# LIDO-HW_300_DisplayInterface.net
KiCad netlist of a schematic drawn in Altium Designer
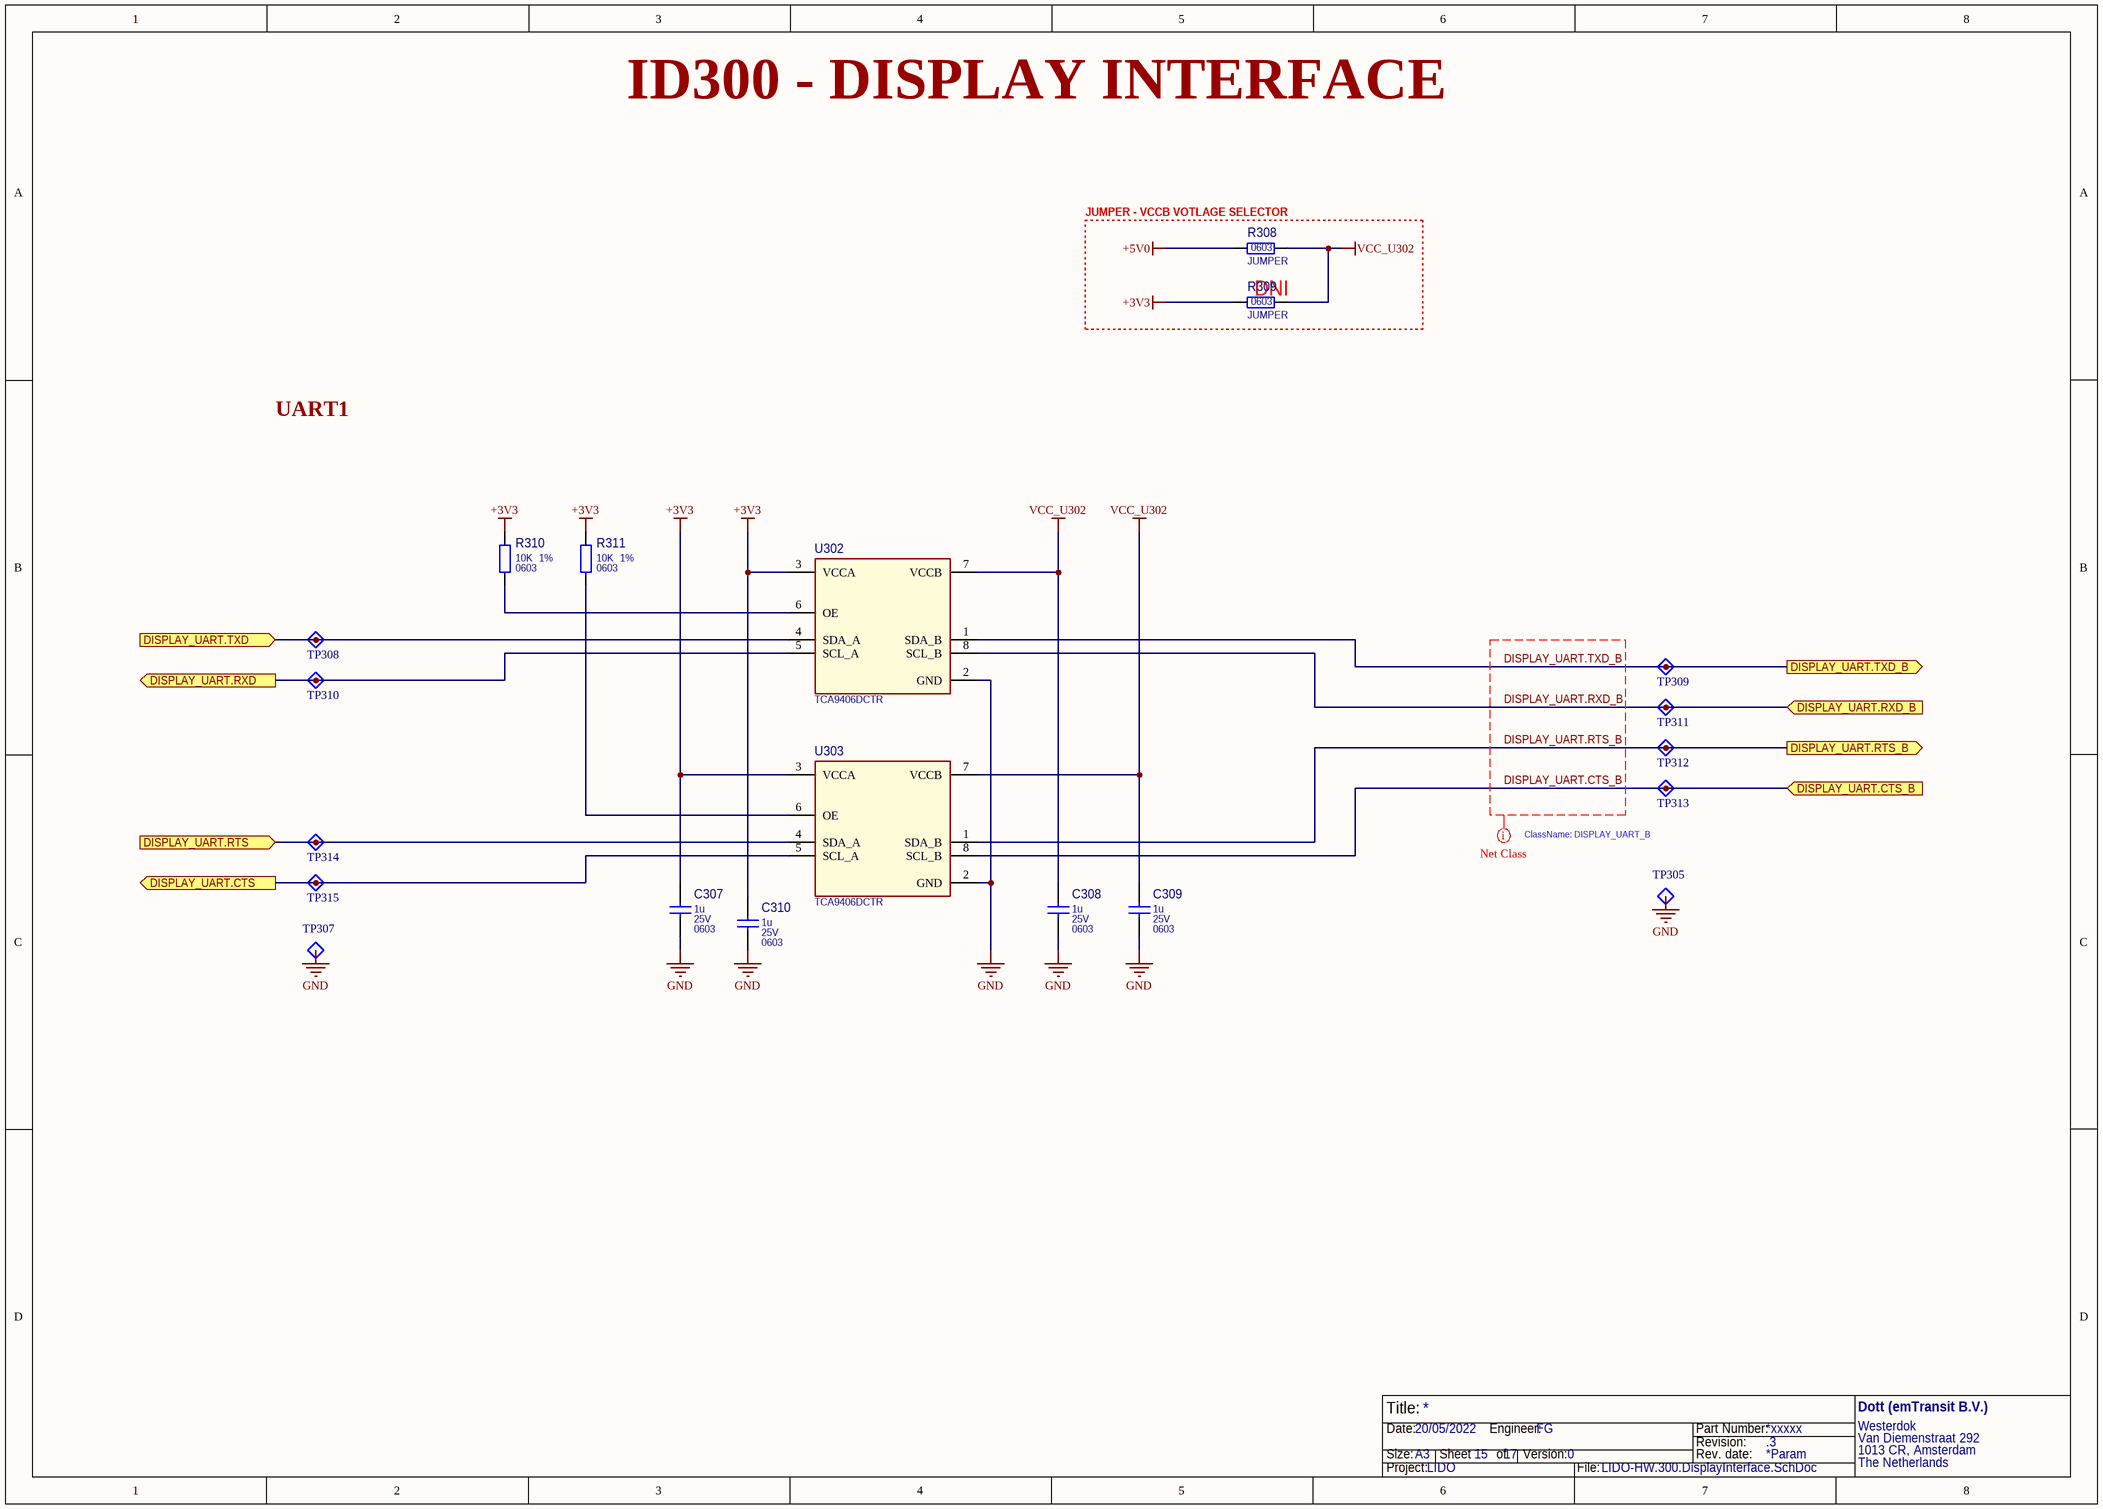
[diagram p0: LIDO-HW.300.DisplayInterface.SchDoc]

(export (version "E")
  (design (tool "Eeschema 10.0.6"))
  (components
    (comp (ref "C307")
      (value "1u")
      (footprint "CAP_0603_1608X90-N_MURATA_A")
      (description "CAP CER 1UF 25V X7R 0603")
      (fields
        (field (name "MANUFACTURER PART NUMBER") "CGA3E1X7R1E105M080AE")
        (field (name "MANUFACTURER") "TDK Corporation")
        (field (name "PART VALUE 2") "25V")
        (field (name "PART PACKAGE") "0603")
      )
      (libsource (lib "DB_Library") (part "Ceramic"))
    )
    (comp (ref "C308")
      (value "1u")
      (footprint "CAP_0603_1608X90-N_MURATA_A")
      (description "CAP CER 1UF 25V X7R 0603")
      (fields
        (field (name "MANUFACTURER PART NUMBER") "CGA3E1X7R1E105M080AE")
        (field (name "MANUFACTURER") "TDK Corporation")
        (field (name "PART VALUE 2") "25V")
        (field (name "PART PACKAGE") "0603")
      )
      (libsource (lib "DB_Library") (part "Ceramic"))
    )
    (comp (ref "C309")
      (value "1u")
      (footprint "CAP_0603_1608X90-N_MURATA_A")
      (description "CAP CER 1UF 25V X7R 0603")
      (fields
        (field (name "MANUFACTURER PART NUMBER") "CGA3E1X7R1E105M080AE")
        (field (name "MANUFACTURER") "TDK Corporation")
        (field (name "PART VALUE 2") "25V")
        (field (name "PART PACKAGE") "0603")
      )
      (libsource (lib "DB_Library") (part "Ceramic"))
    )
    (comp (ref "C310")
      (value "1u")
      (footprint "CAP_0603_1608X90-N_MURATA_A")
      (description "CAP CER 1UF 25V X7R 0603")
      (fields
        (field (name "MANUFACTURER PART NUMBER") "CGA3E1X7R1E105M080AE")
        (field (name "MANUFACTURER") "TDK Corporation")
        (field (name "PART VALUE 2") "25V")
        (field (name "PART PACKAGE") "0603")
      )
      (libsource (lib "DB_Library") (part "Ceramic"))
    )
    (comp (ref "R308")
      (value "JUMPER")
      (footprint "RES_0603_1608X60-N_YAGEO_A")
      (description "RES 0 OHM JUMPER 1/10W 0603")
      (fields
        (field (name "MANUFACTURER PART NUMBER") "RC0603JR-070RL")
        (field (name "MANUFACTURER") "YAGEO")
        (field (name "PART PACKAGE") "0603")
      )
      (libsource (lib "") (part "Resistor_1"))
    )
    (comp (ref "R309")
      (value "JUMPER")
      (footprint "RES_0603_1608X60-N_YAGEO_A")
      (description "RES 0 OHM JUMPER 1/10W 0603")
      (fields
        (field (name "MANUFACTURER PART NUMBER") "RC0603JR-070RL")
        (field (name "MANUFACTURER") "YAGEO")
        (field (name "PART PACKAGE") "0603")
      )
      (libsource (lib "") (part "Resistor_1"))
    )
    (comp (ref "R310")
      (value "10K")
      (footprint "RES_0603_1608X60-N_YAGEO_A")
      (description "RES 10K OHM 1% 1/10W 0603")
      (fields
        (field (name "MANUFACTURER PART NUMBER") "RC0603FR-0710KL")
        (field (name "MANUFACTURER") "YAGEO")
        (field (name "PART VALUE 2") "1%")
        (field (name "PART PACKAGE") "0603")
      )
      (libsource (lib "DB_Library") (part "Resistor"))
    )
    (comp (ref "R311")
      (value "10K")
      (footprint "RES_0603_1608X60-N_YAGEO_A")
      (description "RES 10K OHM 1% 1/10W 0603")
      (fields
        (field (name "MANUFACTURER PART NUMBER") "RC0603FR-0710KL")
        (field (name "MANUFACTURER") "YAGEO")
        (field (name "PART VALUE 2") "1%")
        (field (name "PART PACKAGE") "0603")
      )
      (libsource (lib "DB_Library") (part "Resistor"))
    )
    (comp (ref "TP305")
      (value "TestPoint_A")
      (footprint "TESTPOINT_1D_A")
      (description "Pad Diamater 1mm")
      (fields (field (name "PART") "Test Point 1D A") (field (name "OBSOLETE PART") "False"))
      (libsource (lib "DB_Library") (part "TestPoint_A"))
    )
    (comp (ref "TP307")
      (value "TestPoint_A")
      (footprint "TESTPOINT_1D_A")
      (description "Pad Diamater 1mm")
      (fields (field (name "PART") "Test Point 1D A") (field (name "OBSOLETE PART") "False"))
      (libsource (lib "DB_Library") (part "TestPoint_A"))
    )
    (comp (ref "TP308")
      (value "TestPoint_A")
      (footprint "TESTPOINT_1D_A")
      (description "Pad Diamater 1mm")
      (fields (field (name "PART") "Test Point 1D A") (field (name "OBSOLETE PART") "False"))
      (libsource (lib "DB_Library") (part "TestPoint_A"))
    )
    (comp (ref "TP309")
      (value "TestPoint_A")
      (footprint "TESTPOINT_1D_A")
      (description "Pad Diamater 1mm")
      (fields (field (name "PART") "Test Point 1D A") (field (name "OBSOLETE PART") "False"))
      (libsource (lib "DB_Library") (part "TestPoint_A"))
    )
    (comp (ref "TP310")
      (value "TestPoint_A")
      (footprint "TESTPOINT_1D_A")
      (description "Pad Diamater 1mm")
      (fields (field (name "PART") "Test Point 1D A") (field (name "OBSOLETE PART") "False"))
      (libsource (lib "DB_Library") (part "TestPoint_A"))
    )
    (comp (ref "TP311")
      (value "TestPoint_A")
      (footprint "TESTPOINT_1D_A")
      (description "Pad Diamater 1mm")
      (fields (field (name "PART") "Test Point 1D A") (field (name "OBSOLETE PART") "False"))
      (libsource (lib "DB_Library") (part "TestPoint_A"))
    )
    (comp (ref "TP312")
      (value "TestPoint_A")
      (footprint "TESTPOINT_1D_A")
      (description "Pad Diamater 1mm")
      (fields (field (name "PART") "Test Point 1D A") (field (name "OBSOLETE PART") "False"))
      (libsource (lib "DB_Library") (part "TestPoint_A"))
    )
    (comp (ref "TP313")
      (value "TestPoint_A")
      (footprint "TESTPOINT_1D_A")
      (description "Pad Diamater 1mm")
      (fields (field (name "PART") "Test Point 1D A") (field (name "OBSOLETE PART") "False"))
      (libsource (lib "DB_Library") (part "TestPoint_A"))
    )
    (comp (ref "TP314")
      (value "TestPoint_A")
      (footprint "TESTPOINT_1D_A")
      (description "Pad Diamater 1mm")
      (fields (field (name "PART") "Test Point 1D A") (field (name "OBSOLETE PART") "False"))
      (libsource (lib "DB_Library") (part "TestPoint_A"))
    )
    (comp (ref "TP315")
      (value "TestPoint_A")
      (footprint "TESTPOINT_1D_A")
      (description "Pad Diamater 1mm")
      (fields (field (name "PART") "Test Point 1D A") (field (name "OBSOLETE PART") "False"))
      (libsource (lib "DB_Library") (part "TestPoint_A"))
    )
    (comp (ref "U302")
      (value "TCA9406DCTR")
      (footprint "SSOP8P65_295X400X130L40X25-N_TI_A")
      (description "Voltage Level Translator Bidirectional 1 Circuit 2 Channel 24Mbps SM8")
      (fields (field (name "MANUFACTURER") "Texas Instruments") (field (name "OBSOLETE PART") "False"))
      (libsource (lib "DB_Library") (part "TCA9406_A"))
    )
    (comp (ref "U303")
      (value "TCA9406DCTR")
      (footprint "SSOP8P65_295X400X130L40X25-N_TI_A")
      (description "Voltage Level Translator Bidirectional 1 Circuit 2 Channel 24Mbps SM8")
      (fields (field (name "MANUFACTURER") "Texas Instruments") (field (name "OBSOLETE PART") "False"))
      (libsource (lib "DB_Library") (part "TCA9406_A"))
    )
  )
  (nets
    (net (code "1") (name "+3V3") (class "Default")
      (node (ref "C307") (pin "1") (pinfunction "1_1") (pintype "passive"))
      (node (ref "C310") (pin "1") (pinfunction "1_1") (pintype "passive"))
      (node (ref "R309") (pin "1") (pinfunction "1_1") (pintype "passive"))
      (node (ref "R310") (pin "2") (pinfunction "2_2") (pintype "passive"))
      (node (ref "R311") (pin "2") (pinfunction "2_2") (pintype "passive"))
      (node (ref "U302") (pin "3") (pinfunction "VCCA_3") (pintype "power_in"))
      (node (ref "U303") (pin "3") (pinfunction "VCCA_3") (pintype "power_in"))
    )
    (net (code "2") (name "+5V0") (class "Default")
      (node (ref "R308") (pin "1") (pinfunction "1_1") (pintype "passive"))
    )
    (net (code "3") (name "/DISPLAY_UART.CTS") (class "Default")
      (node (ref "TP315") (pin "1") (pinfunction "TP_1") (pintype "passive"))
      (node (ref "U303") (pin "5") (pinfunction "SCL_A_5") (pintype "passive"))
    )
    (net (code "4") (name "/DISPLAY_UART.CTS_B") (class "Default")
      (node (ref "TP313") (pin "1") (pinfunction "TP_1") (pintype "passive"))
      (node (ref "U303") (pin "8") (pinfunction "SCL_B_8") (pintype "passive"))
    )
    (net (code "5") (name "/DISPLAY_UART.RTS") (class "Default")
      (node (ref "TP314") (pin "1") (pinfunction "TP_1") (pintype "passive"))
      (node (ref "U303") (pin "4") (pinfunction "SDA_A_4") (pintype "passive"))
    )
    (net (code "6") (name "/DISPLAY_UART.RTS_B") (class "Default")
      (node (ref "TP312") (pin "1") (pinfunction "TP_1") (pintype "passive"))
      (node (ref "U303") (pin "1") (pinfunction "SDA_B_1") (pintype "passive"))
    )
    (net (code "7") (name "/DISPLAY_UART.RXD") (class "Default")
      (node (ref "TP310") (pin "1") (pinfunction "TP_1") (pintype "passive"))
      (node (ref "U302") (pin "5") (pinfunction "SCL_A_5") (pintype "passive"))
    )
    (net (code "8") (name "/DISPLAY_UART.RXD_B") (class "Default")
      (node (ref "TP311") (pin "1") (pinfunction "TP_1") (pintype "passive"))
      (node (ref "U302") (pin "8") (pinfunction "SCL_B_8") (pintype "passive"))
    )
    (net (code "9") (name "/DISPLAY_UART.TXD") (class "Default")
      (node (ref "TP308") (pin "1") (pinfunction "TP_1") (pintype "passive"))
      (node (ref "U302") (pin "4") (pinfunction "SDA_A_4") (pintype "passive"))
    )
    (net (code "10") (name "/DISPLAY_UART.TXD_B") (class "Default")
      (node (ref "TP309") (pin "1") (pinfunction "TP_1") (pintype "passive"))
      (node (ref "U302") (pin "1") (pinfunction "SDA_B_1") (pintype "passive"))
    )
    (net (code "11") (name "GND") (class "Default")
      (node (ref "C307") (pin "2") (pinfunction "2_2") (pintype "passive"))
      (node (ref "C308") (pin "2") (pinfunction "2_2") (pintype "passive"))
      (node (ref "C309") (pin "2") (pinfunction "2_2") (pintype "passive"))
      (node (ref "C310") (pin "2") (pinfunction "2_2") (pintype "passive"))
      (node (ref "TP305") (pin "1") (pinfunction "TP_1") (pintype "passive"))
      (node (ref "TP307") (pin "1") (pinfunction "TP_1") (pintype "passive"))
      (node (ref "U302") (pin "2") (pinfunction "GND_2") (pintype "power_in"))
      (node (ref "U303") (pin "2") (pinfunction "GND_2") (pintype "power_in"))
    )
    (net (code "12") (name "Net-(U302-OE)") (class "Default")
      (node (ref "R310") (pin "1") (pinfunction "1_1") (pintype "passive"))
      (node (ref "U302") (pin "6") (pinfunction "OE_6") (pintype "passive"))
    )
    (net (code "13") (name "Net-(U303-OE)") (class "Default")
      (node (ref "R311") (pin "1") (pinfunction "1_1") (pintype "passive"))
      (node (ref "U303") (pin "6") (pinfunction "OE_6") (pintype "passive"))
    )
    (net (code "14") (name "VCC_U302") (class "Default")
      (node (ref "C308") (pin "1") (pinfunction "1_1") (pintype "passive"))
      (node (ref "C309") (pin "1") (pinfunction "1_1") (pintype "passive"))
      (node (ref "R308") (pin "2") (pinfunction "2_2") (pintype "passive"))
      (node (ref "R309") (pin "2") (pinfunction "2_2") (pintype "passive"))
      (node (ref "U302") (pin "7") (pinfunction "VCCB_7") (pintype "power_in"))
      (node (ref "U303") (pin "7") (pinfunction "VCCB_7") (pintype "power_in"))
    )
  )
)
